# Headers.net
KiCad netlist of a schematic drawn in Altium Designer
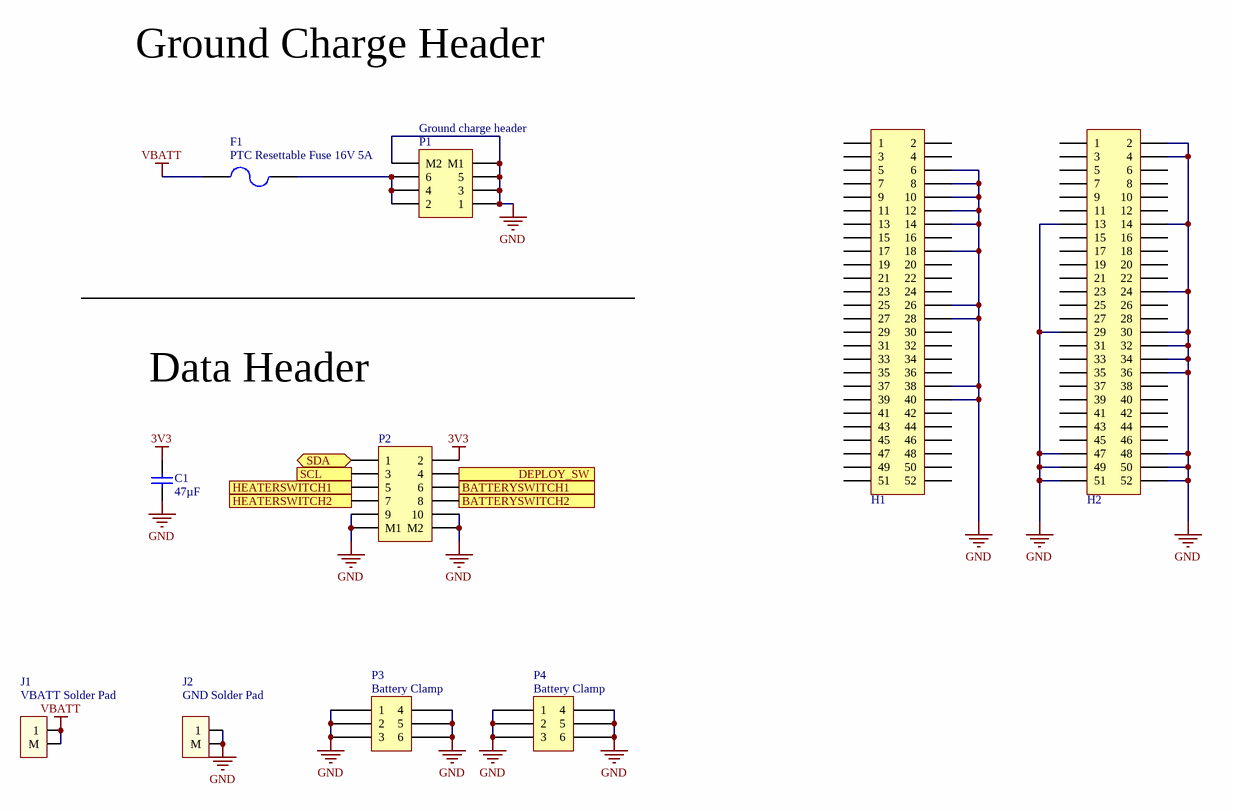
[diagram p0: Headers.SchDoc]

(export (version "E")
  (design (tool "Eeschema 10.0.6"))
  (components
    (comp (ref "C1")
      (value "47µF")
      (footprint "TDK-CGA6P")
      (description "CAP CER 47UF 6.3V X7S 1210")
      (fields
        (field (name "PART NUMBER") "PC-TDK-02951")
        (field (name "MANUFACTURER PART NUMBER") "CGA6P1X7S0J476M250AC")
        (field (name "PUBLISHER") "AlbertaSat")
      )
      (libsource (lib "Database") (part "Cap"))
    )
    (comp (ref "F1")
      (value "PTC Resettable Fuse 16V 5A")
      (footprint "Littelfuse:2920L500/16")
      (description "PTC RESET FUSE 16V 5A 2920")
      (fields
        (field (name "PART NUMBER") "PF-LTF-00001")
        (field (name "MANUFACTURER PART NUMBER") "2920L500/16MR")
        (field (name "PUBLISHER") "AlbertaSat")
      )
      (libsource (lib "Database") (part "Fuse 2"))
    )
    (comp (ref "H1")
      (value "SSW-126-23-G-D")
      (footprint "SSW-126-23-G-D")
      (fields (field (name "PART NUMBER") "PP-SAM-00002") (field (name "PUBLISHER") "AlbertaSat"))
      (libsource (lib "Database") (part "Header 26X2"))
    )
    (comp (ref "H2")
      (value "SSW-126-23-G-D")
      (footprint "SSW-126-23-G-D")
      (fields (field (name "PART NUMBER") "PP-SAM-00002") (field (name "PUBLISHER") "AlbertaSat"))
      (libsource (lib "Database") (part "Header 26X2"))
    )
    (comp (ref "J1")
      (value "VBATT Solder Pad")
      (footprint "Custom-prometheus:VBATT-wire-pad")
      (libsource (lib "Custom-Prometheus") (part "Pad I/O"))
    )
    (comp (ref "J2")
      (value "GND Solder Pad")
      (footprint "Custom-prometheus:GND-WIRE-PAD")
      (libsource (lib "Custom-Prometheus") (part "Pad I/O"))
    )
    (comp (ref "P1")
      (value "G125-MH10605L1")
      (footprint "Harwin Incorporated:HWN-G125-MH10605L1P")
      (description "CONN HEADER R/A 6POS 1.25MM")
      (fields
        (field (name "PART NUMBER") "PP-HWN-00014")
        (field (name "MANUFACTURER PART NUMBER") "G125-MH10605L1P")
        (field (name "PUBLISHER") "AlbertaSat")
      )
      (libsource (lib "Database") (part "Header 4X2"))
    )
    (comp (ref "P2")
      (value "G125-MH11005L1")
      (footprint "Harwin Incorporated:HWN-G125-MH11005L1P")
      (description "CONN HEADER R/A 10POS 1.25MM")
      (fields
        (field (name "PART NUMBER") "PP-HWN-00015")
        (field (name "MANUFACTURER PART NUMBER") "G125-MH11005L1P")
        (field (name "PUBLISHER") "AlbertaSat")
      )
      (libsource (lib "Database") (part "Header 6X2"))
    )
    (comp (ref "P3")
      (value "Battery Clamp")
      (footprint "Custom-prometheus:Battery Clamp")
      (libsource (lib "Custom-Prometheus") (part "Battery Clamp"))
    )
    (comp (ref "P4")
      (value "Battery Clamp")
      (footprint "Custom-prometheus:Battery Clamp")
      (libsource (lib "Custom-Prometheus") (part "Battery Clamp"))
    )
  )
  (nets
    (net (code "1") (name "/BATTERYSWITCH1") (class "Default")
      (node (ref "P2") (pin "6") (pinfunction "6_6") (pintype "passive"))
    )
    (net (code "2") (name "/BATTERYSWITCH2") (class "Default")
      (node (ref "P2") (pin "8") (pinfunction "8_8") (pintype "passive"))
    )
    (net (code "3") (name "/DEPLOY_SW") (class "Default")
      (node (ref "P2") (pin "4") (pinfunction "4_4") (pintype "passive"))
    )
    (net (code "4") (name "/HEATERSWITCH1") (class "Default")
      (node (ref "P2") (pin "5") (pinfunction "5_5") (pintype "passive"))
    )
    (net (code "5") (name "/HEATERSWITCH2") (class "Default")
      (node (ref "P2") (pin "7") (pinfunction "7_7") (pintype "passive"))
    )
    (net (code "6") (name "/SCL") (class "Default")
      (node (ref "P2") (pin "3") (pinfunction "3_3") (pintype "passive"))
    )
    (net (code "7") (name "/SDA") (class "Default")
      (node (ref "P2") (pin "1") (pinfunction "1_1") (pintype "passive"))
    )
    (net (code "8") (name "3V3") (class "Default")
      (node (ref "C1") (pin "2") (pinfunction "2_2") (pintype "passive"))
      (node (ref "P2") (pin "2") (pinfunction "2_2") (pintype "passive"))
    )
    (net (code "9") (name "GND") (class "Default")
      (node (ref "C1") (pin "1") (pinfunction "1_1") (pintype "passive"))
      (node (ref "H1") (pin "10") (pinfunction "10_10") (pintype "passive"))
      (node (ref "H1") (pin "12") (pinfunction "12_12") (pintype "passive"))
      (node (ref "H1") (pin "14") (pinfunction "14_14") (pintype "passive"))
      (node (ref "H1") (pin "18") (pinfunction "18_18") (pintype "passive"))
      (node (ref "H1") (pin "26") (pinfunction "26_26") (pintype "passive"))
      (node (ref "H1") (pin "28") (pinfunction "28_28") (pintype "passive"))
      (node (ref "H1") (pin "38") (pinfunction "38_38") (pintype "passive"))
      (node (ref "H1") (pin "40") (pinfunction "40_40") (pintype "passive"))
      (node (ref "H1") (pin "6") (pinfunction "6_6") (pintype "passive"))
      (node (ref "H1") (pin "8") (pinfunction "8_8") (pintype "passive"))
      (node (ref "H2") (pin "13") (pinfunction "13_13") (pintype "passive"))
      (node (ref "H2") (pin "14") (pinfunction "14_14") (pintype "passive"))
      (node (ref "H2") (pin "2") (pinfunction "2_2") (pintype "passive"))
      (node (ref "H2") (pin "24") (pinfunction "24_24") (pintype "passive"))
      (node (ref "H2") (pin "29") (pinfunction "29_29") (pintype "passive"))
      (node (ref "H2") (pin "30") (pinfunction "30_30") (pintype "passive"))
      (node (ref "H2") (pin "32") (pinfunction "32_32") (pintype "passive"))
      (node (ref "H2") (pin "34") (pinfunction "34_34") (pintype "passive"))
      (node (ref "H2") (pin "36") (pinfunction "36_36") (pintype "passive"))
      (node (ref "H2") (pin "4") (pinfunction "4_4") (pintype "passive"))
      (node (ref "H2") (pin "47") (pinfunction "47_47") (pintype "passive"))
      (node (ref "H2") (pin "48") (pinfunction "48_48") (pintype "passive"))
      (node (ref "H2") (pin "49") (pinfunction "49_49") (pintype "passive"))
      (node (ref "H2") (pin "50") (pinfunction "50_50") (pintype "passive"))
      (node (ref "H2") (pin "51") (pinfunction "51_51") (pintype "passive"))
      (node (ref "H2") (pin "52") (pinfunction "52_52") (pintype "passive"))
      (node (ref "J2") (pin "1") (pinfunction "1_1") (pintype "passive"))
      (node (ref "J2") (pin "2") (pinfunction "M_2") (pintype "passive"))
      (node (ref "P1") (pin "1") (pinfunction "1_1") (pintype "passive"))
      (node (ref "P1") (pin "3") (pinfunction "3_3") (pintype "passive"))
      (node (ref "P1") (pin "5") (pinfunction "5_5") (pintype "passive"))
      (node (ref "P1") (pin "7") (pinfunction "M1_7") (pintype "passive"))
      (node (ref "P1") (pin "8") (pinfunction "M2_8") (pintype "passive"))
      (node (ref "P2") (pin "10") (pinfunction "10_10") (pintype "passive"))
      (node (ref "P2") (pin "11") (pinfunction "M1_11") (pintype "passive"))
      (node (ref "P2") (pin "12") (pinfunction "M2_12") (pintype "passive"))
      (node (ref "P2") (pin "9") (pinfunction "9_9") (pintype "passive"))
      (node (ref "P3") (pin "1") (pinfunction "1_1") (pintype "passive"))
      (node (ref "P3") (pin "2") (pinfunction "2_2") (pintype "passive"))
      (node (ref "P3") (pin "3") (pinfunction "3_3") (pintype "passive"))
      (node (ref "P3") (pin "4") (pinfunction "4_4") (pintype "passive"))
      (node (ref "P3") (pin "5") (pinfunction "5_5") (pintype "passive"))
      (node (ref "P3") (pin "6") (pinfunction "6_6") (pintype "passive"))
      (node (ref "P4") (pin "1") (pinfunction "1_1") (pintype "passive"))
      (node (ref "P4") (pin "2") (pinfunction "2_2") (pintype "passive"))
      (node (ref "P4") (pin "3") (pinfunction "3_3") (pintype "passive"))
      (node (ref "P4") (pin "4") (pinfunction "4_4") (pintype "passive"))
      (node (ref "P4") (pin "5") (pinfunction "5_5") (pintype "passive"))
      (node (ref "P4") (pin "6") (pinfunction "6_6") (pintype "passive"))
    )
    (net (code "10") (name "Net-(F1-Pad2)") (class "Default")
      (node (ref "F1") (pin "2") (pinfunction "2_2") (pintype "passive"))
      (node (ref "P1") (pin "2") (pinfunction "2_2") (pintype "passive"))
      (node (ref "P1") (pin "4") (pinfunction "4_4") (pintype "passive"))
      (node (ref "P1") (pin "6") (pinfunction "6_6") (pintype "passive"))
    )
    (net (code "11") (name "VBATT") (class "Default")
      (node (ref "F1") (pin "1") (pinfunction "1_1") (pintype "passive"))
      (node (ref "J1") (pin "1") (pinfunction "1_1") (pintype "passive"))
      (node (ref "J1") (pin "2") (pinfunction "M_2") (pintype "passive"))
    )
    (net (code "12") (name "unconnected-(H1-Pad1)") (class "Default")
      (node (ref "H1") (pin "1") (pinfunction "1_1") (pintype "passive"))
    )
    (net (code "13") (name "unconnected-(H1-Pad2)") (class "Default")
      (node (ref "H1") (pin "2") (pinfunction "2_2") (pintype "passive"))
    )
    (net (code "14") (name "unconnected-(H1-Pad3)") (class "Default")
      (node (ref "H1") (pin "3") (pinfunction "3_3") (pintype "passive"))
    )
    (net (code "15") (name "unconnected-(H1-Pad4)") (class "Default")
      (node (ref "H1") (pin "4") (pinfunction "4_4") (pintype "passive"))
    )
    (net (code "16") (name "unconnected-(H1-Pad5)") (class "Default")
      (node (ref "H1") (pin "5") (pinfunction "5_5") (pintype "passive"))
    )
    (net (code "17") (name "unconnected-(H1-Pad7)") (class "Default")
      (node (ref "H1") (pin "7") (pinfunction "7_7") (pintype "passive"))
    )
    (net (code "18") (name "unconnected-(H1-Pad9)") (class "Default")
      (node (ref "H1") (pin "9") (pinfunction "9_9") (pintype "passive"))
    )
    (net (code "19") (name "unconnected-(H1-Pad11)") (class "Default")
      (node (ref "H1") (pin "11") (pinfunction "11_11") (pintype "passive"))
    )
    (net (code "20") (name "unconnected-(H1-Pad13)") (class "Default")
      (node (ref "H1") (pin "13") (pinfunction "13_13") (pintype "passive"))
    )
    (net (code "21") (name "unconnected-(H1-Pad15)") (class "Default")
      (node (ref "H1") (pin "15") (pinfunction "15_15") (pintype "passive"))
    )
    (net (code "22") (name "unconnected-(H1-Pad16)") (class "Default")
      (node (ref "H1") (pin "16") (pinfunction "16_16") (pintype "passive"))
    )
    (net (code "23") (name "unconnected-(H1-Pad17)") (class "Default")
      (node (ref "H1") (pin "17") (pinfunction "17_17") (pintype "passive"))
    )
    (net (code "24") (name "unconnected-(H1-Pad19)") (class "Default")
      (node (ref "H1") (pin "19") (pinfunction "19_19") (pintype "passive"))
    )
    (net (code "25") (name "unconnected-(H1-Pad20)") (class "Default")
      (node (ref "H1") (pin "20") (pinfunction "20_20") (pintype "passive"))
    )
    (net (code "26") (name "unconnected-(H1-Pad21)") (class "Default")
      (node (ref "H1") (pin "21") (pinfunction "21_21") (pintype "passive"))
    )
    (net (code "27") (name "unconnected-(H1-Pad22)") (class "Default")
      (node (ref "H1") (pin "22") (pinfunction "22_22") (pintype "passive"))
    )
    (net (code "28") (name "unconnected-(H1-Pad23)") (class "Default")
      (node (ref "H1") (pin "23") (pinfunction "23_23") (pintype "passive"))
    )
    (net (code "29") (name "unconnected-(H1-Pad24)") (class "Default")
      (node (ref "H1") (pin "24") (pinfunction "24_24") (pintype "passive"))
    )
    (net (code "30") (name "unconnected-(H1-Pad25)") (class "Default")
      (node (ref "H1") (pin "25") (pinfunction "25_25") (pintype "passive"))
    )
    (net (code "31") (name "unconnected-(H1-Pad27)") (class "Default")
      (node (ref "H1") (pin "27") (pinfunction "27_27") (pintype "passive"))
    )
    (net (code "32") (name "unconnected-(H1-Pad29)") (class "Default")
      (node (ref "H1") (pin "29") (pinfunction "29_29") (pintype "passive"))
    )
    (net (code "33") (name "unconnected-(H1-Pad30)") (class "Default")
      (node (ref "H1") (pin "30") (pinfunction "30_30") (pintype "passive"))
    )
    (net (code "34") (name "unconnected-(H1-Pad31)") (class "Default")
      (node (ref "H1") (pin "31") (pinfunction "31_31") (pintype "passive"))
    )
    (net (code "35") (name "unconnected-(H1-Pad32)") (class "Default")
      (node (ref "H1") (pin "32") (pinfunction "32_32") (pintype "passive"))
    )
    (net (code "36") (name "unconnected-(H1-Pad33)") (class "Default")
      (node (ref "H1") (pin "33") (pinfunction "33_33") (pintype "passive"))
    )
    (net (code "37") (name "unconnected-(H1-Pad34)") (class "Default")
      (node (ref "H1") (pin "34") (pinfunction "34_34") (pintype "passive"))
    )
    (net (code "38") (name "unconnected-(H1-Pad35)") (class "Default")
      (node (ref "H1") (pin "35") (pinfunction "35_35") (pintype "passive"))
    )
    (net (code "39") (name "unconnected-(H1-Pad36)") (class "Default")
      (node (ref "H1") (pin "36") (pinfunction "36_36") (pintype "passive"))
    )
    (net (code "40") (name "unconnected-(H1-Pad37)") (class "Default")
      (node (ref "H1") (pin "37") (pinfunction "37_37") (pintype "passive"))
    )
    (net (code "41") (name "unconnected-(H1-Pad39)") (class "Default")
      (node (ref "H1") (pin "39") (pinfunction "39_39") (pintype "passive"))
    )
    (net (code "42") (name "unconnected-(H1-Pad41)") (class "Default")
      (node (ref "H1") (pin "41") (pinfunction "41_41") (pintype "passive"))
    )
    (net (code "43") (name "unconnected-(H1-Pad42)") (class "Default")
      (node (ref "H1") (pin "42") (pinfunction "42_42") (pintype "passive"))
    )
    (net (code "44") (name "unconnected-(H1-Pad43)") (class "Default")
      (node (ref "H1") (pin "43") (pinfunction "43_43") (pintype "passive"))
    )
    (net (code "45") (name "unconnected-(H1-Pad44)") (class "Default")
      (node (ref "H1") (pin "44") (pinfunction "44_44") (pintype "passive"))
    )
    (net (code "46") (name "unconnected-(H1-Pad45)") (class "Default")
      (node (ref "H1") (pin "45") (pinfunction "45_45") (pintype "passive"))
    )
    (net (code "47") (name "unconnected-(H1-Pad46)") (class "Default")
      (node (ref "H1") (pin "46") (pinfunction "46_46") (pintype "passive"))
    )
    (net (code "48") (name "unconnected-(H1-Pad47)") (class "Default")
      (node (ref "H1") (pin "47") (pinfunction "47_47") (pintype "passive"))
    )
    (net (code "49") (name "unconnected-(H1-Pad48)") (class "Default")
      (node (ref "H1") (pin "48") (pinfunction "48_48") (pintype "passive"))
    )
    (net (code "50") (name "unconnected-(H1-Pad49)") (class "Default")
      (node (ref "H1") (pin "49") (pinfunction "49_49") (pintype "passive"))
    )
    (net (code "51") (name "unconnected-(H1-Pad50)") (class "Default")
      (node (ref "H1") (pin "50") (pinfunction "50_50") (pintype "passive"))
    )
    (net (code "52") (name "unconnected-(H1-Pad51)") (class "Default")
      (node (ref "H1") (pin "51") (pinfunction "51_51") (pintype "passive"))
    )
    (net (code "53") (name "unconnected-(H1-Pad52)") (class "Default")
      (node (ref "H1") (pin "52") (pinfunction "52_52") (pintype "passive"))
    )
    (net (code "54") (name "unconnected-(H2-Pad1)") (class "Default")
      (node (ref "H2") (pin "1") (pinfunction "1_1") (pintype "passive"))
    )
    (net (code "55") (name "unconnected-(H2-Pad3)") (class "Default")
      (node (ref "H2") (pin "3") (pinfunction "3_3") (pintype "passive"))
    )
    (net (code "56") (name "unconnected-(H2-Pad5)") (class "Default")
      (node (ref "H2") (pin "5") (pinfunction "5_5") (pintype "passive"))
    )
    (net (code "57") (name "unconnected-(H2-Pad6)") (class "Default")
      (node (ref "H2") (pin "6") (pinfunction "6_6") (pintype "passive"))
    )
    (net (code "58") (name "unconnected-(H2-Pad7)") (class "Default")
      (node (ref "H2") (pin "7") (pinfunction "7_7") (pintype "passive"))
    )
    (net (code "59") (name "unconnected-(H2-Pad8)") (class "Default")
      (node (ref "H2") (pin "8") (pinfunction "8_8") (pintype "passive"))
    )
    (net (code "60") (name "unconnected-(H2-Pad9)") (class "Default")
      (node (ref "H2") (pin "9") (pinfunction "9_9") (pintype "passive"))
    )
    (net (code "61") (name "unconnected-(H2-Pad10)") (class "Default")
      (node (ref "H2") (pin "10") (pinfunction "10_10") (pintype "passive"))
    )
    (net (code "62") (name "unconnected-(H2-Pad11)") (class "Default")
      (node (ref "H2") (pin "11") (pinfunction "11_11") (pintype "passive"))
    )
    (net (code "63") (name "unconnected-(H2-Pad12)") (class "Default")
      (node (ref "H2") (pin "12") (pinfunction "12_12") (pintype "passive"))
    )
    (net (code "64") (name "unconnected-(H2-Pad15)") (class "Default")
      (node (ref "H2") (pin "15") (pinfunction "15_15") (pintype "passive"))
    )
    (net (code "65") (name "unconnected-(H2-Pad16)") (class "Default")
      (node (ref "H2") (pin "16") (pinfunction "16_16") (pintype "passive"))
    )
    (net (code "66") (name "unconnected-(H2-Pad17)") (class "Default")
      (node (ref "H2") (pin "17") (pinfunction "17_17") (pintype "passive"))
    )
    (net (code "67") (name "unconnected-(H2-Pad18)") (class "Default")
      (node (ref "H2") (pin "18") (pinfunction "18_18") (pintype "passive"))
    )
    (net (code "68") (name "unconnected-(H2-Pad19)") (class "Default")
      (node (ref "H2") (pin "19") (pinfunction "19_19") (pintype "passive"))
    )
    (net (code "69") (name "unconnected-(H2-Pad20)") (class "Default")
      (node (ref "H2") (pin "20") (pinfunction "20_20") (pintype "passive"))
    )
    (net (code "70") (name "unconnected-(H2-Pad21)") (class "Default")
      (node (ref "H2") (pin "21") (pinfunction "21_21") (pintype "passive"))
    )
    (net (code "71") (name "unconnected-(H2-Pad22)") (class "Default")
      (node (ref "H2") (pin "22") (pinfunction "22_22") (pintype "passive"))
    )
    (net (code "72") (name "unconnected-(H2-Pad23)") (class "Default")
      (node (ref "H2") (pin "23") (pinfunction "23_23") (pintype "passive"))
    )
    (net (code "73") (name "unconnected-(H2-Pad25)") (class "Default")
      (node (ref "H2") (pin "25") (pinfunction "25_25") (pintype "passive"))
    )
    (net (code "74") (name "unconnected-(H2-Pad26)") (class "Default")
      (node (ref "H2") (pin "26") (pinfunction "26_26") (pintype "passive"))
    )
    (net (code "75") (name "unconnected-(H2-Pad27)") (class "Default")
      (node (ref "H2") (pin "27") (pinfunction "27_27") (pintype "passive"))
    )
    (net (code "76") (name "unconnected-(H2-Pad28)") (class "Default")
      (node (ref "H2") (pin "28") (pinfunction "28_28") (pintype "passive"))
    )
    (net (code "77") (name "unconnected-(H2-Pad31)") (class "Default")
      (node (ref "H2") (pin "31") (pinfunction "31_31") (pintype "passive"))
    )
    (net (code "78") (name "unconnected-(H2-Pad33)") (class "Default")
      (node (ref "H2") (pin "33") (pinfunction "33_33") (pintype "passive"))
    )
    (net (code "79") (name "unconnected-(H2-Pad35)") (class "Default")
      (node (ref "H2") (pin "35") (pinfunction "35_35") (pintype "passive"))
    )
    (net (code "80") (name "unconnected-(H2-Pad37)") (class "Default")
      (node (ref "H2") (pin "37") (pinfunction "37_37") (pintype "passive"))
    )
    (net (code "81") (name "unconnected-(H2-Pad38)") (class "Default")
      (node (ref "H2") (pin "38") (pinfunction "38_38") (pintype "passive"))
    )
    (net (code "82") (name "unconnected-(H2-Pad39)") (class "Default")
      (node (ref "H2") (pin "39") (pinfunction "39_39") (pintype "passive"))
    )
    (net (code "83") (name "unconnected-(H2-Pad40)") (class "Default")
      (node (ref "H2") (pin "40") (pinfunction "40_40") (pintype "passive"))
    )
    (net (code "84") (name "unconnected-(H2-Pad41)") (class "Default")
      (node (ref "H2") (pin "41") (pinfunction "41_41") (pintype "passive"))
    )
    (net (code "85") (name "unconnected-(H2-Pad42)") (class "Default")
      (node (ref "H2") (pin "42") (pinfunction "42_42") (pintype "passive"))
    )
    (net (code "86") (name "unconnected-(H2-Pad43)") (class "Default")
      (node (ref "H2") (pin "43") (pinfunction "43_43") (pintype "passive"))
    )
    (net (code "87") (name "unconnected-(H2-Pad44)") (class "Default")
      (node (ref "H2") (pin "44") (pinfunction "44_44") (pintype "passive"))
    )
    (net (code "88") (name "unconnected-(H2-Pad45)") (class "Default")
      (node (ref "H2") (pin "45") (pinfunction "45_45") (pintype "passive"))
    )
    (net (code "89") (name "unconnected-(H2-Pad46)") (class "Default")
      (node (ref "H2") (pin "46") (pinfunction "46_46") (pintype "passive"))
    )
  )
)
